# pcb.net
KiCad netlist of a schematic drawn in EAGLE
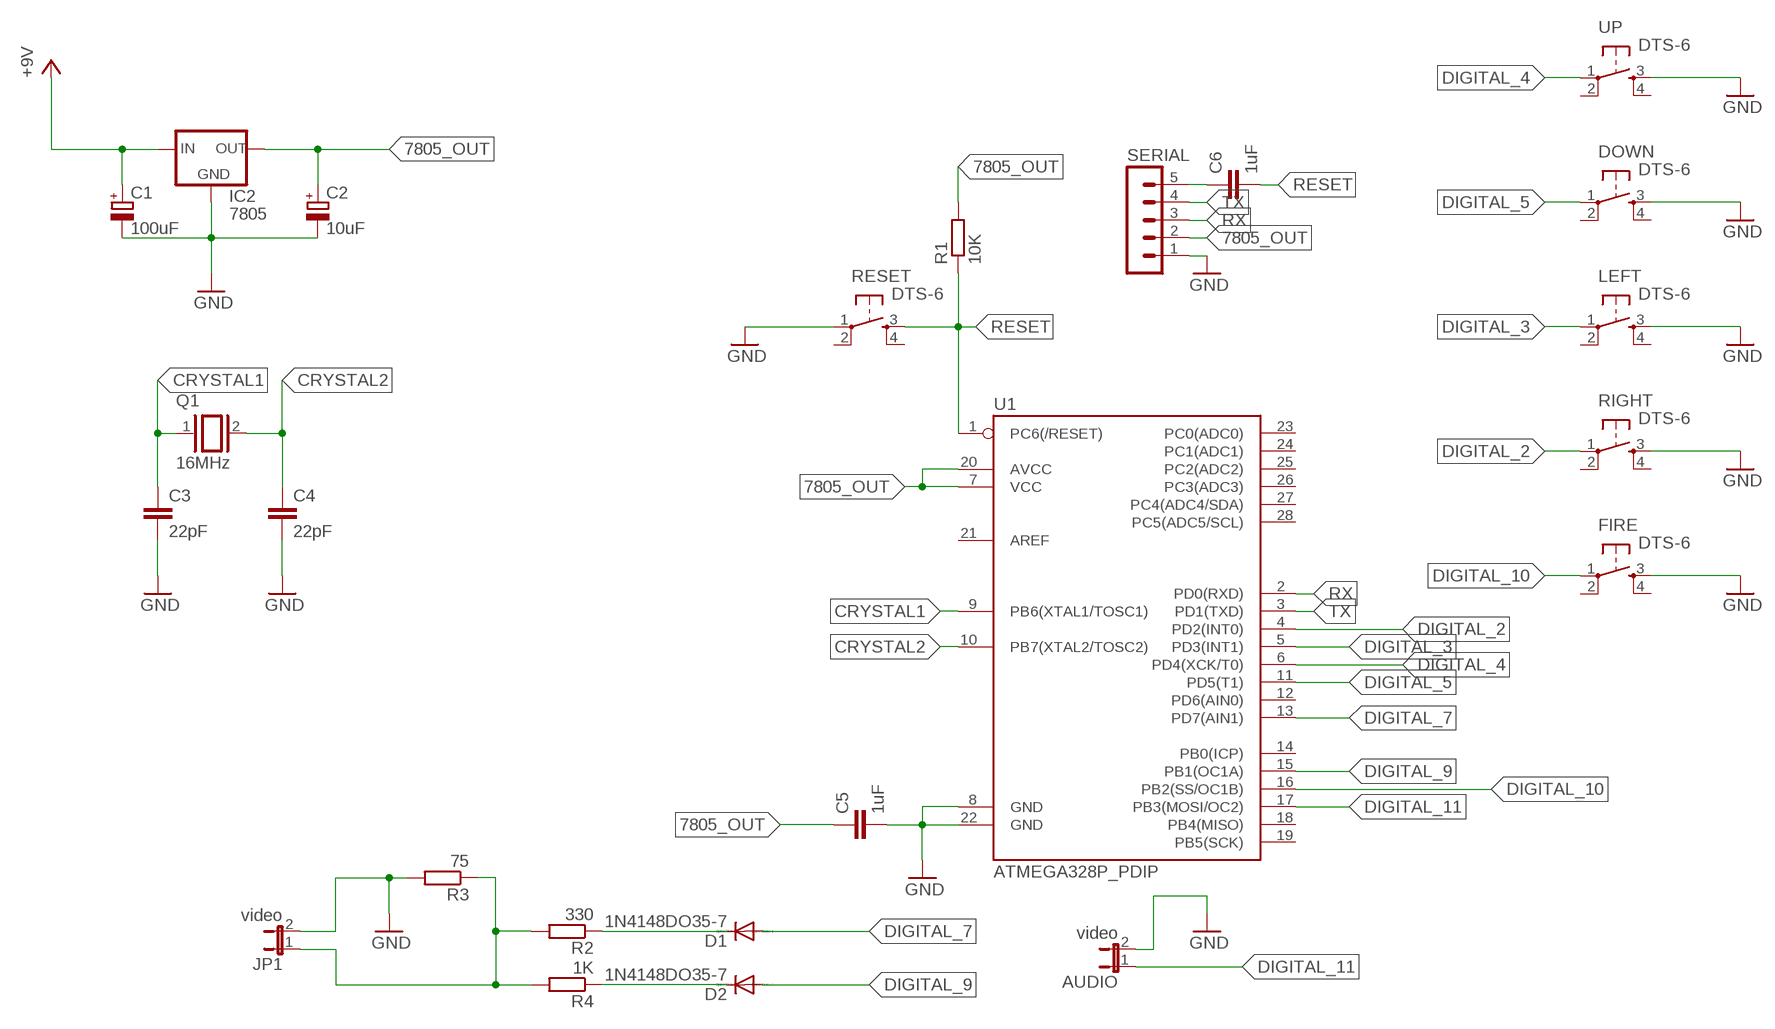
[diagram p0: schematic, sheet 1]

(export (version "E")
  (design (tool "Eeschema 10.0.6"))
  (components
    (comp (ref "AUDIO")
      (value "video")
      (footprint "eagle-import:JP1")
      (libsource (lib "eagle-import") (part "JP1E"))
    )
    (comp (ref "C1")
      (value "100uF")
      (footprint "eagle-import:E2,5-6E")
      (libsource (lib "eagle-import") (part "CPOL-EUE2,5-6E"))
    )
    (comp (ref "C2")
      (value "10uF")
      (footprint "eagle-import:E2,5-6E")
      (libsource (lib "eagle-import") (part "CPOL-EUE2,5-6E"))
    )
    (comp (ref "C3")
      (value "22pF")
      (footprint "eagle-import:C2.5-3")
      (libsource (lib "eagle-import") (part "C2,5-3"))
    )
    (comp (ref "C4")
      (value "22pF")
      (footprint "eagle-import:C2.5-3")
      (libsource (lib "eagle-import") (part "C2,5-3"))
    )
    (comp (ref "C5")
      (value "1uF")
      (footprint "eagle-import:C2.5-3")
      (libsource (lib "eagle-import") (part "C2,5-3"))
    )
    (comp (ref "C6")
      (value "1uF")
      (footprint "eagle-import:C2.5-3")
      (libsource (lib "eagle-import") (part "C2,5-3"))
    )
    (comp (ref "D1")
      (value "1N4148DO35-7")
      (footprint "eagle-import:DO35-7")
      (libsource (lib "eagle-import") (part "1N4148DO35-7"))
    )
    (comp (ref "D2")
      (value "1N4148DO35-7")
      (footprint "eagle-import:DO35-7")
      (libsource (lib "eagle-import") (part "1N4148DO35-7"))
    )
    (comp (ref "DOWN")
      (value "DTS-6")
      (footprint "eagle-import:DTS-6")
      (libsource (lib "eagle-import") (part "DTS-6"))
    )
    (comp (ref "FIRE")
      (value "DTS-6")
      (footprint "eagle-import:DTS-6")
      (libsource (lib "eagle-import") (part "DTS-6"))
    )
    (comp (ref "IC2")
      (value "7805")
      (footprint "eagle-import:78MXXL")
      (libsource (lib "eagle-import") (part "78MXXL"))
    )
    (comp (ref "JP1")
      (value "video")
      (footprint "eagle-import:JP1")
      (libsource (lib "eagle-import") (part "JP1E"))
    )
    (comp (ref "LEFT")
      (value "DTS-6")
      (footprint "eagle-import:DTS-6")
      (libsource (lib "eagle-import") (part "DTS-6"))
    )
    (comp (ref "Q1")
      (value "16MHz")
      (footprint "eagle-import:QS")
      (libsource (lib "eagle-import") (part "XTAL/S"))
    )
    (comp (ref "R1")
      (value "10K")
      (footprint "eagle-import:0204_5")
      (libsource (lib "eagle-import") (part "R-EU_0204/5"))
    )
    (comp (ref "R2")
      (value "330")
      (footprint "eagle-import:0204_5")
      (libsource (lib "eagle-import") (part "R-EU_0204/5"))
    )
    (comp (ref "R3")
      (value "75")
      (footprint "eagle-import:0204_5")
      (libsource (lib "eagle-import") (part "R-EU_0204/5"))
    )
    (comp (ref "R4")
      (value "1K")
      (footprint "eagle-import:0204_5")
      (libsource (lib "eagle-import") (part "R-EU_0204/5"))
    )
    (comp (ref "RESET")
      (value "DTS-6")
      (footprint "eagle-import:DTS-6")
      (libsource (lib "eagle-import") (part "DTS-6"))
    )
    (comp (ref "RIGHT")
      (value "DTS-6")
      (footprint "eagle-import:DTS-6")
      (libsource (lib "eagle-import") (part "DTS-6"))
    )
    (comp (ref "SERIAL")
      (value "MA05-1")
      (footprint "eagle-import:MA05-1")
      (libsource (lib "eagle-import") (part "MA05-1"))
    )
    (comp (ref "U1")
      (value "ATMEGA328P_PDIP")
      (footprint "eagle-import:DIL28-3")
      (libsource (lib "eagle-import") (part "ATMEGA328P_PDIP"))
    )
    (comp (ref "UP")
      (value "DTS-6")
      (footprint "eagle-import:DTS-6")
      (libsource (lib "eagle-import") (part "DTS-6"))
    )
  )
  (nets
    (net (code "1") (name "+9V") (class "Default")
      (node (ref "C1") (pin "+") (pinfunction "+_+") (pintype "passive"))
      (node (ref "IC2") (pin "IN") (pinfunction "IN_IN") (pintype "input"))
    )
    (net (code "2") (name "7805_OUT") (class "Default")
      (node (ref "C2") (pin "+") (pinfunction "+_+") (pintype "passive"))
      (node (ref "C5") (pin "1") (pinfunction "1_1") (pintype "passive"))
      (node (ref "IC2") (pin "OUT") (pinfunction "OUT_OUT") (pintype "passive"))
      (node (ref "R1") (pin "2") (pinfunction "2_2") (pintype "passive"))
      (node (ref "SERIAL") (pin "2") (pinfunction "2_2") (pintype "passive"))
      (node (ref "U1") (pin "20") (pinfunction "AVCC_20") (pintype "bidirectional"))
      (node (ref "U1") (pin "7") (pinfunction "VCC_7") (pintype "bidirectional"))
    )
    (net (code "3") (name "CRYSTAL1") (class "Default")
      (node (ref "C3") (pin "1") (pinfunction "1_1") (pintype "passive"))
      (node (ref "Q1") (pin "1") (pinfunction "1_1") (pintype "passive"))
      (node (ref "U1") (pin "9") (pinfunction "PB6(XTAL1/TOSC1)_9") (pintype "bidirectional"))
    )
    (net (code "4") (name "CRYSTAL2") (class "Default")
      (node (ref "C4") (pin "1") (pinfunction "1_1") (pintype "passive"))
      (node (ref "Q1") (pin "2") (pinfunction "2_2") (pintype "passive"))
      (node (ref "U1") (pin "10") (pinfunction "PB7(XTAL2/TOSC2)_10") (pintype "bidirectional"))
    )
    (net (code "5") (name "DIGITAL_2") (class "Default")
      (node (ref "RIGHT") (pin "1") (pinfunction "1_1") (pintype "passive"))
      (node (ref "U1") (pin "4") (pinfunction "PD2(INT0)_4") (pintype "bidirectional"))
    )
    (net (code "6") (name "DIGITAL_3") (class "Default")
      (node (ref "LEFT") (pin "1") (pinfunction "1_1") (pintype "passive"))
      (node (ref "U1") (pin "5") (pinfunction "PD3(INT1)_5") (pintype "bidirectional"))
    )
    (net (code "7") (name "DIGITAL_4") (class "Default")
      (node (ref "U1") (pin "6") (pinfunction "PD4(XCK/T0)_6") (pintype "bidirectional"))
      (node (ref "UP") (pin "1") (pinfunction "1_1") (pintype "passive"))
    )
    (net (code "8") (name "DIGITAL_5") (class "Default")
      (node (ref "DOWN") (pin "1") (pinfunction "1_1") (pintype "passive"))
      (node (ref "U1") (pin "11") (pinfunction "PD5(T1)_11") (pintype "bidirectional"))
    )
    (net (code "9") (name "DIGITAL_7") (class "Default")
      (node (ref "D1") (pin "A") (pinfunction "A_A") (pintype "passive"))
      (node (ref "U1") (pin "13") (pinfunction "PD7(AIN1)_13") (pintype "bidirectional"))
    )
    (net (code "10") (name "DIGITAL_9") (class "Default")
      (node (ref "D2") (pin "A") (pinfunction "A_A") (pintype "passive"))
      (node (ref "U1") (pin "15") (pinfunction "PB1(OC1A)_15") (pintype "bidirectional"))
    )
    (net (code "11") (name "DIGITAL_10") (class "Default")
      (node (ref "FIRE") (pin "1") (pinfunction "1_1") (pintype "passive"))
      (node (ref "U1") (pin "16") (pinfunction "PB2(SS/OC1B)_16") (pintype "bidirectional"))
    )
    (net (code "12") (name "DIGITAL_11") (class "Default")
      (node (ref "AUDIO") (pin "1") (pinfunction "1_1") (pintype "passive"))
      (node (ref "U1") (pin "17") (pinfunction "PB3(MOSI/OC2)_17") (pintype "bidirectional"))
    )
    (net (code "13") (name "GND") (class "Default")
      (node (ref "AUDIO") (pin "2") (pinfunction "2_2") (pintype "passive"))
      (node (ref "C1") (pin "-") (pinfunction "-_-") (pintype "passive"))
      (node (ref "C2") (pin "-") (pinfunction "-_-") (pintype "passive"))
      (node (ref "C3") (pin "2") (pinfunction "2_2") (pintype "passive"))
      (node (ref "C4") (pin "2") (pinfunction "2_2") (pintype "passive"))
      (node (ref "C5") (pin "2") (pinfunction "2_2") (pintype "passive"))
      (node (ref "DOWN") (pin "3") (pinfunction "3_3") (pintype "passive"))
      (node (ref "FIRE") (pin "3") (pinfunction "3_3") (pintype "passive"))
      (node (ref "IC2") (pin "GND") (pinfunction "GND_GND") (pintype "input"))
      (node (ref "JP1") (pin "2") (pinfunction "2_2") (pintype "passive"))
      (node (ref "LEFT") (pin "3") (pinfunction "3_3") (pintype "passive"))
      (node (ref "R3") (pin "2") (pinfunction "2_2") (pintype "passive"))
      (node (ref "RESET") (pin "1") (pinfunction "1_1") (pintype "passive"))
      (node (ref "RIGHT") (pin "3") (pinfunction "3_3") (pintype "passive"))
      (node (ref "SERIAL") (pin "1") (pinfunction "1_1") (pintype "passive"))
      (node (ref "U1") (pin "22") (pinfunction "GND_22") (pintype "bidirectional"))
      (node (ref "U1") (pin "8") (pinfunction "GND_8") (pintype "bidirectional"))
      (node (ref "UP") (pin "3") (pinfunction "3_3") (pintype "passive"))
    )
    (net (code "14") (name "Net-(C6-Pad1)") (class "Default")
      (node (ref "C6") (pin "1") (pinfunction "1_1") (pintype "passive"))
      (node (ref "SERIAL") (pin "5") (pinfunction "5_5") (pintype "passive"))
    )
    (net (code "15") (name "Net-(D1-PadC)") (class "Default")
      (node (ref "D1") (pin "C") (pinfunction "C_C") (pintype "passive"))
      (node (ref "R2") (pin "1") (pinfunction "1_1") (pintype "passive"))
    )
    (net (code "16") (name "Net-(D2-PadC)") (class "Default")
      (node (ref "D2") (pin "C") (pinfunction "C_C") (pintype "passive"))
      (node (ref "R4") (pin "1") (pinfunction "1_1") (pintype "passive"))
    )
    (net (code "17") (name "Net-(JP1-Pad1)") (class "Default")
      (node (ref "JP1") (pin "1") (pinfunction "1_1") (pintype "passive"))
      (node (ref "R2") (pin "2") (pinfunction "2_2") (pintype "passive"))
      (node (ref "R3") (pin "1") (pinfunction "1_1") (pintype "passive"))
      (node (ref "R4") (pin "2") (pinfunction "2_2") (pintype "passive"))
    )
    (net (code "18") (name "RESET") (class "Default")
      (node (ref "C6") (pin "2") (pinfunction "2_2") (pintype "passive"))
      (node (ref "R1") (pin "1") (pinfunction "1_1") (pintype "passive"))
      (node (ref "RESET") (pin "3") (pinfunction "3_3") (pintype "passive"))
      (node (ref "U1") (pin "1") (pinfunction "PC6(/RESET)_1") (pintype "bidirectional"))
    )
    (net (code "19") (name "RX") (class "Default")
      (node (ref "SERIAL") (pin "3") (pinfunction "3_3") (pintype "passive"))
      (node (ref "U1") (pin "2") (pinfunction "PD0(RXD)_2") (pintype "bidirectional"))
    )
    (net (code "20") (name "TX") (class "Default")
      (node (ref "SERIAL") (pin "4") (pinfunction "4_4") (pintype "passive"))
      (node (ref "U1") (pin "3") (pinfunction "PD1(TXD)_3") (pintype "bidirectional"))
    )
    (net (code "21") (name "unconnected-(DOWN-Pad2)") (class "Default")
      (node (ref "DOWN") (pin "2") (pinfunction "2_2") (pintype "passive"))
    )
    (net (code "22") (name "unconnected-(DOWN-Pad4)") (class "Default")
      (node (ref "DOWN") (pin "4") (pinfunction "4_4") (pintype "passive"))
    )
    (net (code "23") (name "unconnected-(FIRE-Pad2)") (class "Default")
      (node (ref "FIRE") (pin "2") (pinfunction "2_2") (pintype "passive"))
    )
    (net (code "24") (name "unconnected-(FIRE-Pad4)") (class "Default")
      (node (ref "FIRE") (pin "4") (pinfunction "4_4") (pintype "passive"))
    )
    (net (code "25") (name "unconnected-(LEFT-Pad2)") (class "Default")
      (node (ref "LEFT") (pin "2") (pinfunction "2_2") (pintype "passive"))
    )
    (net (code "26") (name "unconnected-(LEFT-Pad4)") (class "Default")
      (node (ref "LEFT") (pin "4") (pinfunction "4_4") (pintype "passive"))
    )
    (net (code "27") (name "unconnected-(RESET-Pad2)") (class "Default")
      (node (ref "RESET") (pin "2") (pinfunction "2_2") (pintype "passive"))
    )
    (net (code "28") (name "unconnected-(RESET-Pad4)") (class "Default")
      (node (ref "RESET") (pin "4") (pinfunction "4_4") (pintype "passive"))
    )
    (net (code "29") (name "unconnected-(RIGHT-Pad2)") (class "Default")
      (node (ref "RIGHT") (pin "2") (pinfunction "2_2") (pintype "passive"))
    )
    (net (code "30") (name "unconnected-(RIGHT-Pad4)") (class "Default")
      (node (ref "RIGHT") (pin "4") (pinfunction "4_4") (pintype "passive"))
    )
    (net (code "31") (name "unconnected-(U1-AREF-Pad21)") (class "Default")
      (node (ref "U1") (pin "21") (pinfunction "AREF_21") (pintype "bidirectional"))
    )
    (net (code "32") (name "unconnected-(U1-PB0(ICP)-Pad14)") (class "Default")
      (node (ref "U1") (pin "14") (pinfunction "PB0(ICP)_14") (pintype "bidirectional"))
    )
    (net (code "33") (name "unconnected-(U1-PB4(MISO)-Pad18)") (class "Default")
      (node (ref "U1") (pin "18") (pinfunction "PB4(MISO)_18") (pintype "bidirectional"))
    )
    (net (code "34") (name "unconnected-(U1-PB5(SCK)-Pad19)") (class "Default")
      (node (ref "U1") (pin "19") (pinfunction "PB5(SCK)_19") (pintype "bidirectional"))
    )
    (net (code "35") (name "unconnected-(U1-PC0(ADC0)-Pad23)") (class "Default")
      (node (ref "U1") (pin "23") (pinfunction "PC0(ADC0)_23") (pintype "bidirectional"))
    )
    (net (code "36") (name "unconnected-(U1-PC1(ADC1)-Pad24)") (class "Default")
      (node (ref "U1") (pin "24") (pinfunction "PC1(ADC1)_24") (pintype "bidirectional"))
    )
    (net (code "37") (name "unconnected-(U1-PC2(ADC2)-Pad25)") (class "Default")
      (node (ref "U1") (pin "25") (pinfunction "PC2(ADC2)_25") (pintype "bidirectional"))
    )
    (net (code "38") (name "unconnected-(U1-PC3(ADC3)-Pad26)") (class "Default")
      (node (ref "U1") (pin "26") (pinfunction "PC3(ADC3)_26") (pintype "bidirectional"))
    )
    (net (code "39") (name "unconnected-(U1-PC4(ADC4{slash}SDA)-Pad27)") (class "Default")
      (node (ref "U1") (pin "27") (pinfunction "PC4(ADC4/SDA)_27") (pintype "bidirectional"))
    )
    (net (code "40") (name "unconnected-(U1-PC5(ADC5{slash}SCL)-Pad28)") (class "Default")
      (node (ref "U1") (pin "28") (pinfunction "PC5(ADC5/SCL)_28") (pintype "bidirectional"))
    )
    (net (code "41") (name "unconnected-(U1-PD6(AIN0)-Pad12)") (class "Default")
      (node (ref "U1") (pin "12") (pinfunction "PD6(AIN0)_12") (pintype "bidirectional"))
    )
    (net (code "42") (name "unconnected-(UP-Pad2)") (class "Default")
      (node (ref "UP") (pin "2") (pinfunction "2_2") (pintype "passive"))
    )
    (net (code "43") (name "unconnected-(UP-Pad4)") (class "Default")
      (node (ref "UP") (pin "4") (pinfunction "4_4") (pintype "passive"))
    )
  )
)
